# PowerDistributionBoard.net
KiCad netlist of a schematic drawn in EAGLE
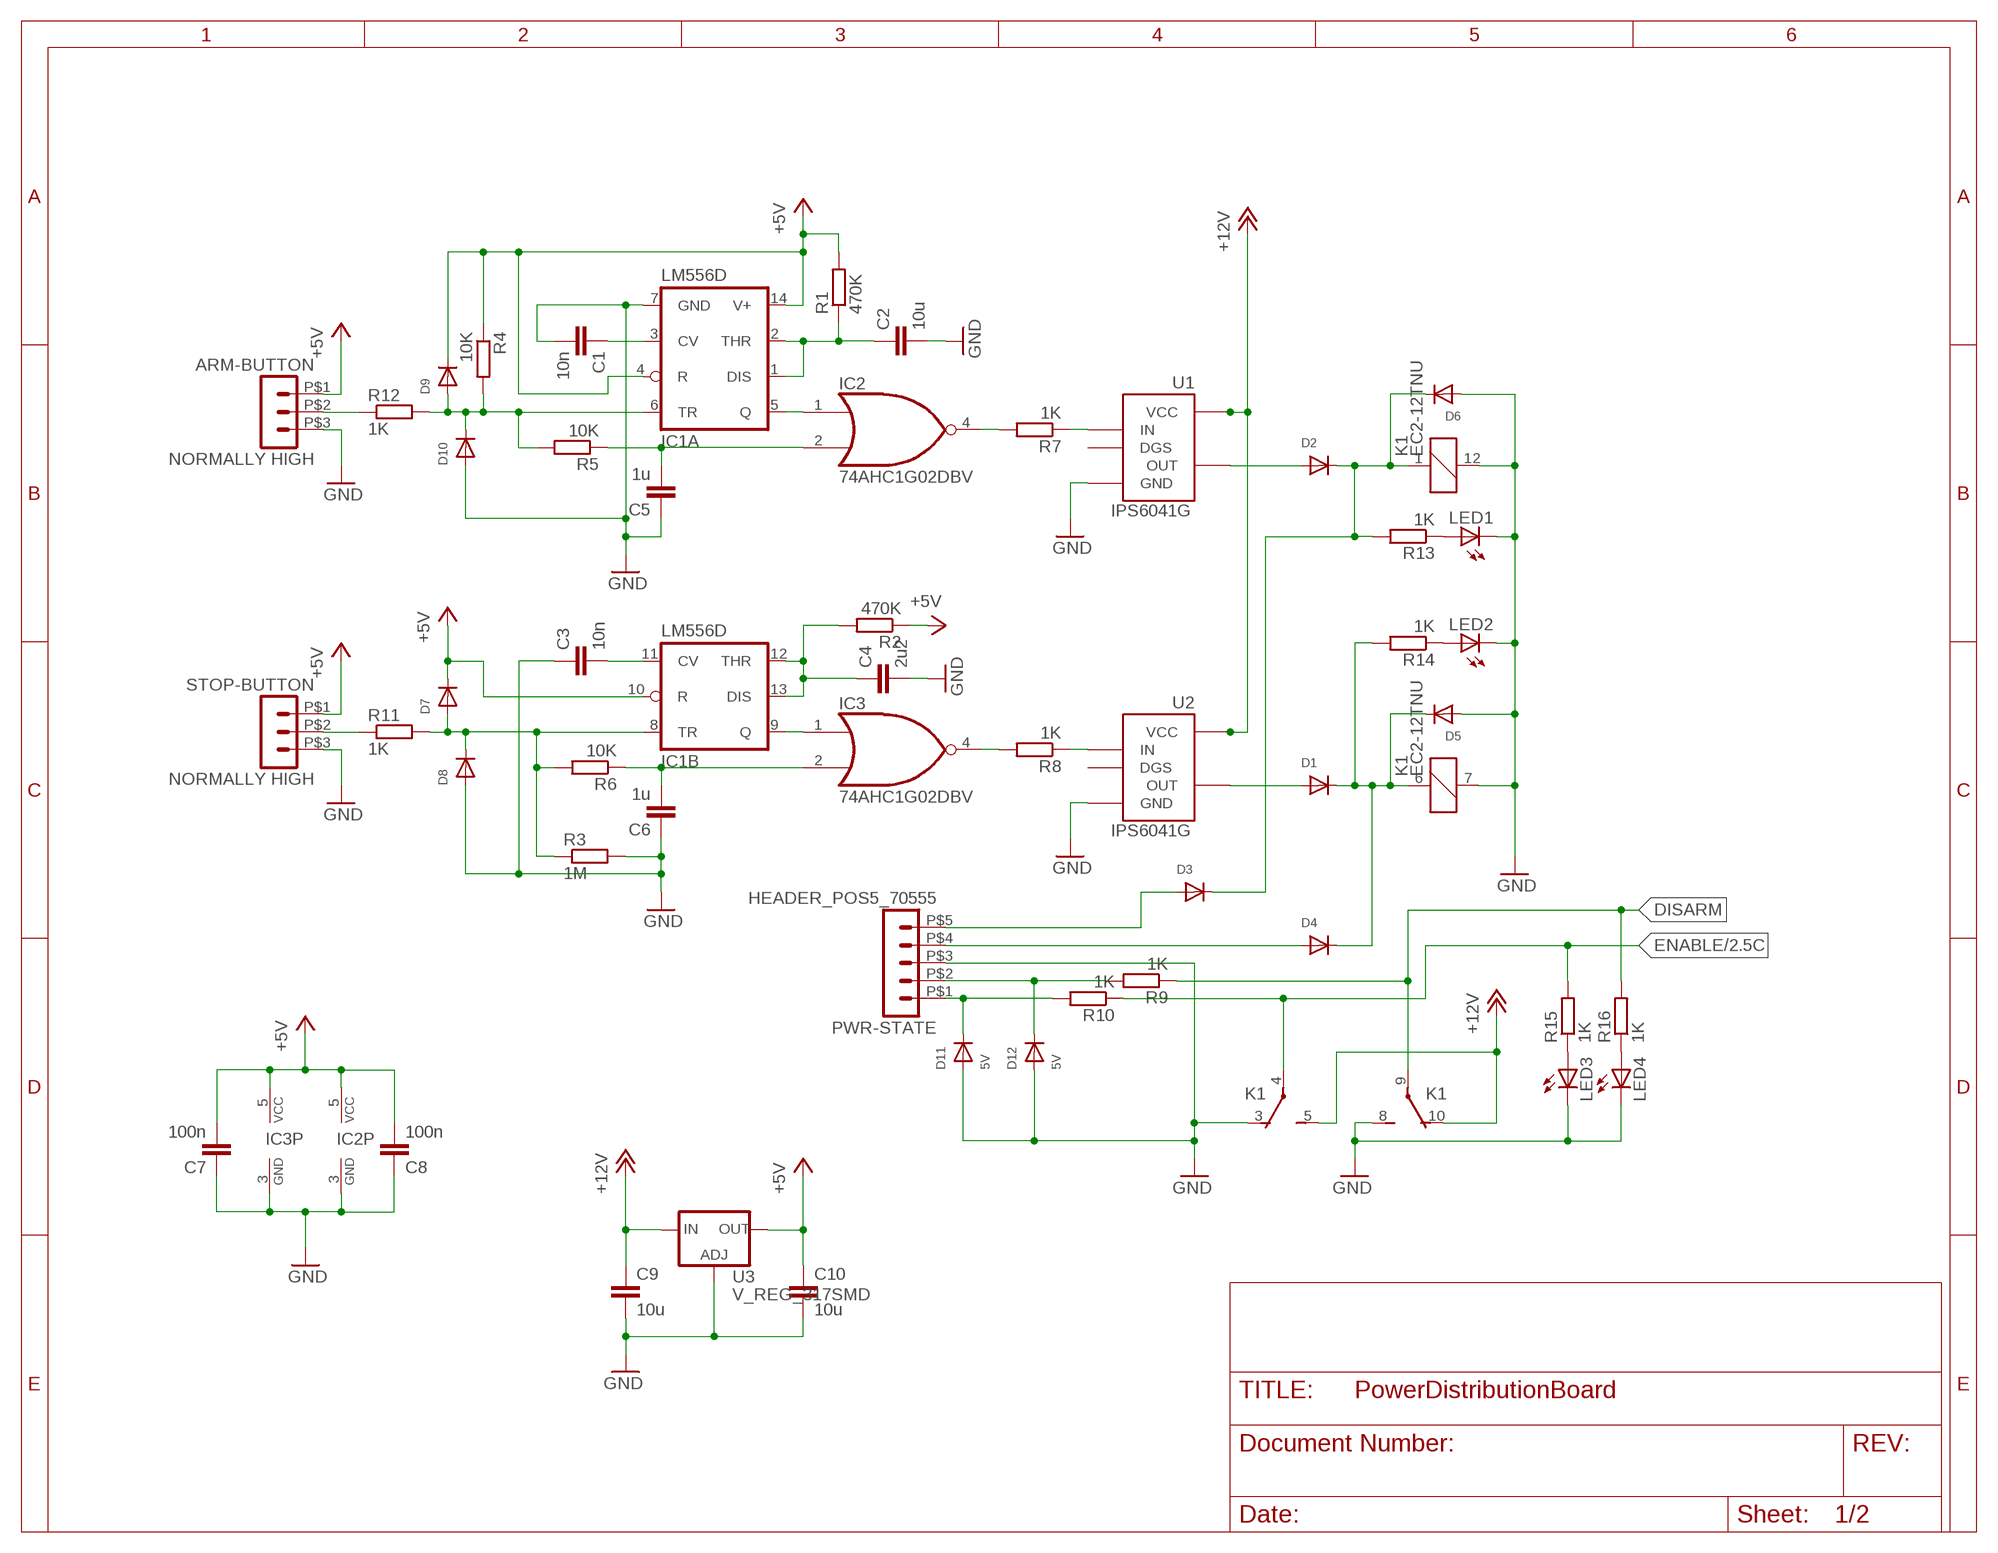
[diagram p0: schematic, sheet 1]
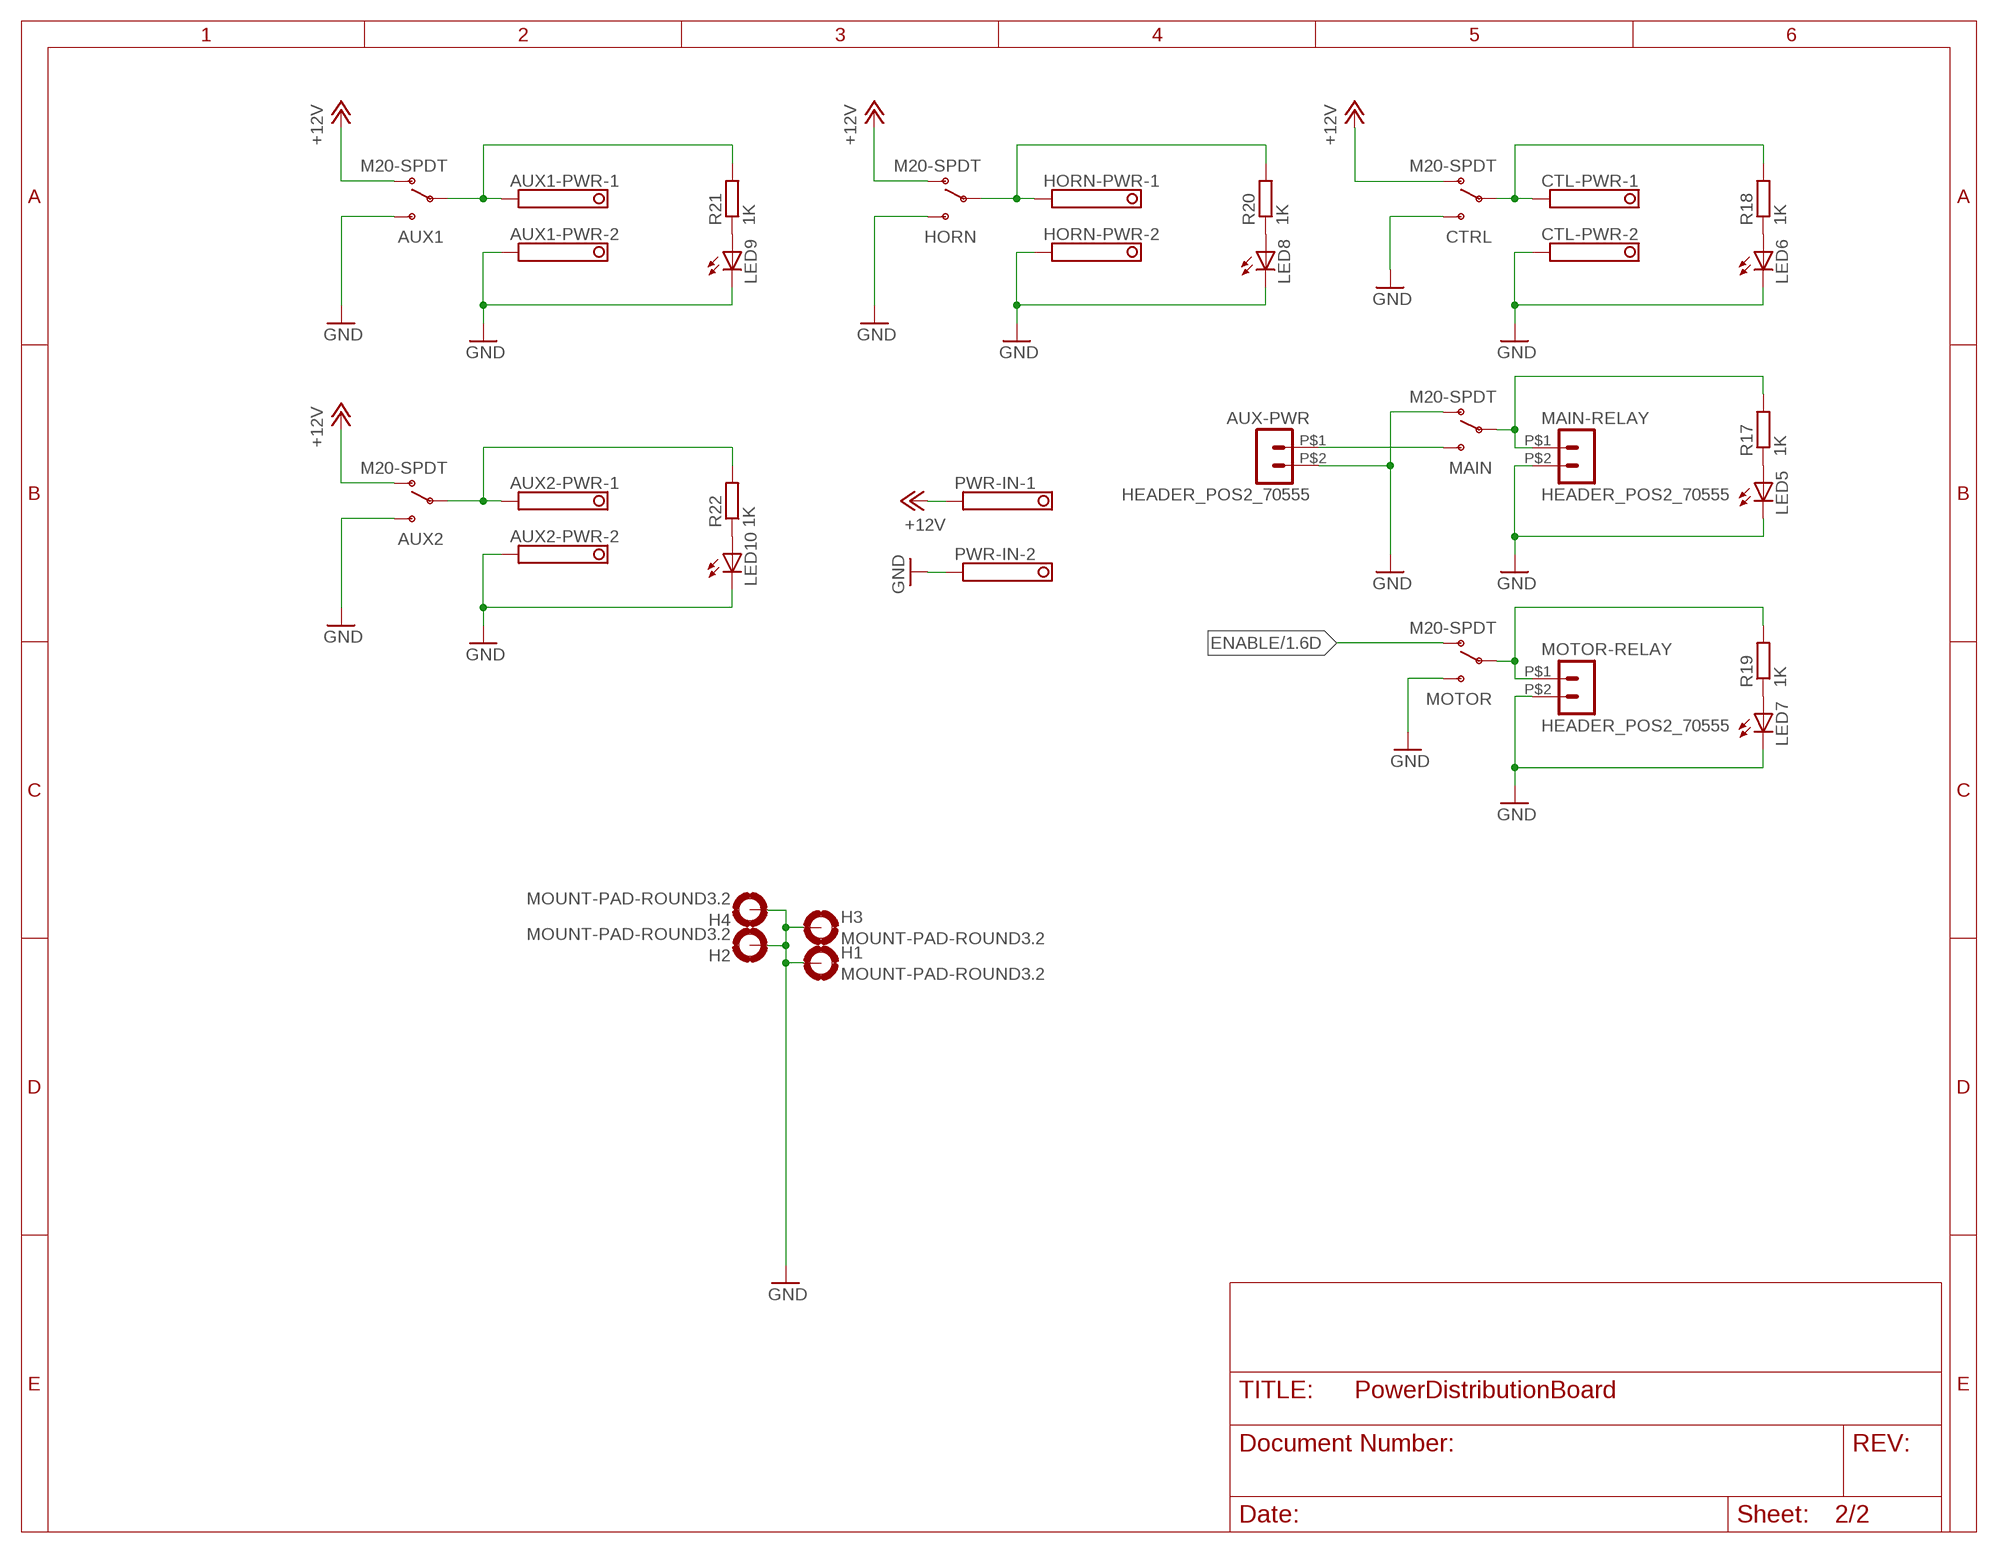
[diagram p1: schematic, sheet 2]

(export (version "E")
  (design (tool "Eeschema 10.0.6"))
  (components
    (comp (ref "ARM-BUTTON")
      (value "NORMALLY HIGH")
      (footprint "eagle-import:70555-POS3")
      (fields (field (name "PARTNO") "0705550037"))
      (libsource (lib "eagle-import") (part "HEADER_POS3_?70555"))
    )
    (comp (ref "C1")
      (value "10n")
      (footprint "eagle-import:C0603")
      (fields (field (name "PARTNO") "CL10B103KB8NCNC"))
      (libsource (lib "eagle-import") (part "C-EUC0603"))
    )
    (comp (ref "C2")
      (value "10u")
      (footprint "eagle-import:C0603")
      (fields (field (name "PARTNO") "C1608JB1E106M080AC"))
      (libsource (lib "eagle-import") (part "C-EUC0603"))
    )
    (comp (ref "C3")
      (value "10n")
      (footprint "eagle-import:C0603")
      (fields (field (name "PARTNO") "CL10B103KB8NCNC"))
      (libsource (lib "eagle-import") (part "C-EUC0603"))
    )
    (comp (ref "C4")
      (value "2u2")
      (footprint "eagle-import:C0603")
      (fields (field (name "PARTNO") "TMK107ABJ225KA-T"))
      (libsource (lib "eagle-import") (part "C-EUC0603"))
    )
    (comp (ref "C5")
      (value "1u")
      (footprint "eagle-import:C0603")
      (fields (field (name "PARTNO") "UMK107BJ105KA-T"))
      (libsource (lib "eagle-import") (part "C-EUC0603"))
    )
    (comp (ref "C6")
      (value "1u")
      (footprint "eagle-import:C0603")
      (fields (field (name "PARTNO") "UMK107BJ105KA-T"))
      (libsource (lib "eagle-import") (part "C-EUC0603"))
    )
    (comp (ref "C7")
      (value "100n")
      (footprint "eagle-import:C0603")
      (fields (field (name "PARTNO") "CC0603ZRY5V9BB104"))
      (libsource (lib "eagle-import") (part "C-EUC0603"))
    )
    (comp (ref "C8")
      (value "100n")
      (footprint "eagle-import:C0603")
      (fields (field (name "PARTNO") "CC0603ZRY5V9BB104"))
      (libsource (lib "eagle-import") (part "C-EUC0603"))
    )
    (comp (ref "C9")
      (value "10u")
      (footprint "eagle-import:C1206")
      (fields (field (name "PARTNO") "C3216X5R1E106M"))
      (libsource (lib "eagle-import") (part "C-EUC1206"))
    )
    (comp (ref "C10")
      (value "10u")
      (footprint "eagle-import:C1206")
      (fields (field (name "PARTNO") "C3216X5R1E106M"))
      (libsource (lib "eagle-import") (part "C-EUC1206"))
    )
    (comp (ref "D1")
      (value "DIODESOD-123")
      (footprint "eagle-import:SOD-123")
      (fields (field (name "PARTNO") "CDBW140-G"))
      (libsource (lib "eagle-import") (part "DIODESOD-123"))
    )
    (comp (ref "D2")
      (value "DIODESOD-123")
      (footprint "eagle-import:SOD-123")
      (fields (field (name "PARTNO") "CDBW140-G"))
      (libsource (lib "eagle-import") (part "DIODESOD-123"))
    )
    (comp (ref "D3")
      (value "DIODESOD-123")
      (footprint "eagle-import:SOD-123")
      (fields (field (name "PARTNO") "CDBW140-G"))
      (libsource (lib "eagle-import") (part "DIODESOD-123"))
    )
    (comp (ref "D4")
      (value "DIODESOD-123")
      (footprint "eagle-import:SOD-123")
      (fields (field (name "PARTNO") "CDBW140-G"))
      (libsource (lib "eagle-import") (part "DIODESOD-123"))
    )
    (comp (ref "D5")
      (value "DIODESOD-123")
      (footprint "eagle-import:SOD-123")
      (fields (field (name "PARTNO") "CDBW140-G"))
      (libsource (lib "eagle-import") (part "DIODESOD-123"))
    )
    (comp (ref "D6")
      (value "DIODESOD-123")
      (footprint "eagle-import:SOD-123")
      (fields (field (name "PARTNO") "CDBW140-G"))
      (libsource (lib "eagle-import") (part "DIODESOD-123"))
    )
    (comp (ref "D7")
      (value "DIODESOD-123")
      (footprint "eagle-import:SOD-123")
      (fields (field (name "PARTNO") "CDBW140-G"))
      (libsource (lib "eagle-import") (part "DIODESOD-123"))
    )
    (comp (ref "D8")
      (value "DIODESOD-123")
      (footprint "eagle-import:SOD-123")
      (fields (field (name "PARTNO") "CDBW140-G"))
      (libsource (lib "eagle-import") (part "DIODESOD-123"))
    )
    (comp (ref "D9")
      (value "DIODESOD-123")
      (footprint "eagle-import:SOD-123")
      (fields (field (name "PARTNO") "CDBW140-G"))
      (libsource (lib "eagle-import") (part "DIODESOD-123"))
    )
    (comp (ref "D10")
      (value "DIODESOD-123")
      (footprint "eagle-import:SOD-123")
      (fields (field (name "PARTNO") "CDBW140-G"))
      (libsource (lib "eagle-import") (part "DIODESOD-123"))
    )
    (comp (ref "D11")
      (value "5V")
      (footprint "eagle-import:SOD-123")
      (fields (field (name "PARTNO") "SMF5.0A"))
      (libsource (lib "eagle-import") (part "DIODESOD-123"))
    )
    (comp (ref "D12")
      (value "5V")
      (footprint "eagle-import:SOD-123")
      (fields (field (name "PARTNO") "SMF5.0A"))
      (libsource (lib "eagle-import") (part "DIODESOD-123"))
    )
    (comp (ref "IC1")
      (value "LM556D")
      (footprint "eagle-import:SO14")
      (fields (field (name "PARTNO") "LM556CM"))
      (libsource (lib "eagle-import") (part "556DLM"))
    )
    (comp (ref "IC2")
      (value "74AHC1G02DBV")
      (footprint "eagle-import:SOT23-5")
      (fields (field (name "PARTNO") "SN74AHC1G02DBVR"))
      (libsource (lib "eagle-import") (part "741G02DBVAHC"))
    )
    (comp (ref "IC3")
      (value "74AHC1G02DBV")
      (footprint "eagle-import:SOT23-5")
      (fields (field (name "PARTNO") "SN74AHC1G02DBVR"))
      (libsource (lib "eagle-import") (part "741G02DBVAHC"))
    )
    (comp (ref "K1")
      (value "EC2-12TNU")
      (footprint "eagle-import:EC2-_TNU")
      (fields (field (name "PARTNO") "EC2-12TNU"))
      (libsource (lib "eagle-import") (part "EC2-12TNU"))
    )
    (comp (ref "LED1")
      (value "LEDCHIP-LED0805")
      (footprint "eagle-import:CHIP-LED0805")
      (fields (field (name "PARTNO") "LG R971-KN-1"))
      (libsource (lib "eagle-import") (part "LEDCHIP-LED0805"))
    )
    (comp (ref "LED2")
      (value "LEDCHIP-LED0805")
      (footprint "eagle-import:CHIP-LED0805")
      (fields (field (name "PARTNO") "LG R971-KN-1"))
      (libsource (lib "eagle-import") (part "LEDCHIP-LED0805"))
    )
    (comp (ref "LED3")
      (value "LEDCHIP-LED0805")
      (footprint "eagle-import:CHIP-LED0805")
      (fields (field (name "PARTNO") "LG R971-KN-1"))
      (libsource (lib "eagle-import") (part "LEDCHIP-LED0805"))
    )
    (comp (ref "LED4")
      (value "LEDCHIP-LED0805")
      (footprint "eagle-import:CHIP-LED0805")
      (fields (field (name "PARTNO") "LG R971-KN-1"))
      (libsource (lib "eagle-import") (part "LEDCHIP-LED0805"))
    )
    (comp (ref "PWR-STATE")
      (value "HEADER_POS5_70555")
      (footprint "eagle-import:70555-POS5")
      (fields (field (name "PARTNO") "0705550039"))
      (libsource (lib "eagle-import") (part "HEADER_POS5_?70555"))
    )
    (comp (ref "R1")
      (value "470K")
      (footprint "eagle-import:R0603")
      (fields (field (name "PARTNO") "MCR03FZPEJ474"))
      (libsource (lib "eagle-import") (part "R-EU_R0603"))
    )
    (comp (ref "R2")
      (value "470K")
      (footprint "eagle-import:R0603")
      (fields (field (name "PARTNO") "MCR03FZPEJ474"))
      (libsource (lib "eagle-import") (part "R-EU_R0603"))
    )
    (comp (ref "R3")
      (value "1M")
      (footprint "eagle-import:R0603")
      (fields (field (name "PARTNO") "MCT06030C1004FP500"))
      (libsource (lib "eagle-import") (part "R-EU_R0603"))
    )
    (comp (ref "R4")
      (value "10K")
      (footprint "eagle-import:R0603")
      (fields (field (name "PARTNO") "RMCF0603FT10K0"))
      (libsource (lib "eagle-import") (part "R-EU_R0603"))
    )
    (comp (ref "R5")
      (value "10K")
      (footprint "eagle-import:R0603")
      (fields (field (name "PARTNO") "RMCF0603FT10K0"))
      (libsource (lib "eagle-import") (part "R-EU_R0603"))
    )
    (comp (ref "R6")
      (value "10K")
      (footprint "eagle-import:R0603")
      (fields (field (name "PARTNO") "RMCF0603FT10K0"))
      (libsource (lib "eagle-import") (part "R-EU_R0603"))
    )
    (comp (ref "R7")
      (value "1K")
      (footprint "eagle-import:R0603")
      (fields (field (name "PARTNO") "RMCF0603FT1K00"))
      (libsource (lib "eagle-import") (part "R-EU_R0603"))
    )
    (comp (ref "R8")
      (value "1K")
      (footprint "eagle-import:R0603")
      (fields (field (name "PARTNO") "RMCF0603FT1K00"))
      (libsource (lib "eagle-import") (part "R-EU_R0603"))
    )
    (comp (ref "R9")
      (value "1K")
      (footprint "eagle-import:R0603")
      (fields (field (name "PARTNO") "RMCF0603FT1K00"))
      (libsource (lib "eagle-import") (part "R-EU_R0603"))
    )
    (comp (ref "R10")
      (value "1K")
      (footprint "eagle-import:R0603")
      (fields (field (name "PARTNO") "RMCF0603FT1K00"))
      (libsource (lib "eagle-import") (part "R-EU_R0603"))
    )
    (comp (ref "R11")
      (value "1K")
      (footprint "eagle-import:R0603")
      (fields (field (name "PARTNO") "RMCF0603FT1K00"))
      (libsource (lib "eagle-import") (part "R-EU_R0603"))
    )
    (comp (ref "R12")
      (value "1K")
      (footprint "eagle-import:R0603")
      (fields (field (name "PARTNO") "RMCF0603FT1K00"))
      (libsource (lib "eagle-import") (part "R-EU_R0603"))
    )
    (comp (ref "R13")
      (value "1K")
      (footprint "eagle-import:R0603")
      (fields (field (name "PARTNO") "RMCF0603FT1K00"))
      (libsource (lib "eagle-import") (part "R-EU_R0603"))
    )
    (comp (ref "R14")
      (value "1K")
      (footprint "eagle-import:R0603")
      (fields (field (name "PARTNO") "RMCF0603FT1K00"))
      (libsource (lib "eagle-import") (part "R-EU_R0603"))
    )
    (comp (ref "R15")
      (value "1K")
      (footprint "eagle-import:R0603")
      (fields (field (name "PARTNO") "RMCF0603FT1K00"))
      (libsource (lib "eagle-import") (part "R-EU_R0603"))
    )
    (comp (ref "R16")
      (value "1K")
      (footprint "eagle-import:R0603")
      (fields (field (name "PARTNO") "RMCF0603FT1K00"))
      (libsource (lib "eagle-import") (part "R-EU_R0603"))
    )
    (comp (ref "STOP-BUTTON")
      (value "NORMALLY HIGH")
      (footprint "eagle-import:70555-POS3")
      (fields (field (name "PARTNO") "0705550037"))
      (libsource (lib "eagle-import") (part "HEADER_POS3_?70555"))
    )
    (comp (ref "U1")
      (value "IPS6041G")
      (footprint "eagle-import:SO08")
      (fields (field (name "PARTNO") "IPS6041GPBF"))
      (libsource (lib "eagle-import") (part "IPS6041G"))
    )
    (comp (ref "U2")
      (value "IPS6041G")
      (footprint "eagle-import:SO08")
      (fields (field (name "PARTNO") "IPS6041GPBF"))
      (libsource (lib "eagle-import") (part "IPS6041G"))
    )
    (comp (ref "U3")
      (value "V_REG_317SMD")
      (footprint "eagle-import:SOT223")
      (fields (field (name "PARTNO") "NCP1117ST50T3G"))
      (libsource (lib "eagle-import") (part "V_REG_317SMD"))
    )
    (comp (ref "AUX-PWR")
      (value "HEADER_POS2_70555")
      (footprint "eagle-import:70555-POS2")
      (fields (field (name "PARTNO") "0705550036"))
      (libsource (lib "eagle-import") (part "HEADER_POS2_?70555"))
    )
    (comp (ref "AUX1")
      (value "M20-SPDT")
      (footprint "eagle-import:M20-SPDT")
      (fields (field (name "PARTNO") "M2012LL1W01"))
      (libsource (lib "eagle-import") (part "M20-SPDT"))
    )
    (comp (ref "AUX1-PWR")
      (value "1751248")
      (footprint "eagle-import:1751248")
      (fields (field (name "PARTNO") "1751248"))
      (libsource (lib "eagle-import") (part "1751248"))
    )
    (comp (ref "AUX2")
      (value "M20-SPDT")
      (footprint "eagle-import:M20-SPDT")
      (fields (field (name "PARTNO") "M2012LL1W01"))
      (libsource (lib "eagle-import") (part "M20-SPDT"))
    )
    (comp (ref "AUX2-PWR")
      (value "1751248")
      (footprint "eagle-import:1751248")
      (fields (field (name "PARTNO") "1751248"))
      (libsource (lib "eagle-import") (part "1751248"))
    )
    (comp (ref "CTL-PWR")
      (value "1751248")
      (footprint "eagle-import:1751248")
      (fields (field (name "PARTNO") "1751248"))
      (libsource (lib "eagle-import") (part "1751248"))
    )
    (comp (ref "CTRL")
      (value "M20-SPDT")
      (footprint "eagle-import:M20-SPDT")
      (fields (field (name "PARTNO") "M2012LL1W01"))
      (libsource (lib "eagle-import") (part "M20-SPDT"))
    )
    (comp (ref "H1")
      (value "MOUNT-PAD-ROUND3.2")
      (footprint "eagle-import:3,2-PAD")
      (libsource (lib "eagle-import") (part "MOUNT-PAD-ROUND3.2"))
    )
    (comp (ref "H2")
      (value "MOUNT-PAD-ROUND3.2")
      (footprint "eagle-import:3,2-PAD")
      (libsource (lib "eagle-import") (part "MOUNT-PAD-ROUND3.2"))
    )
    (comp (ref "H3")
      (value "MOUNT-PAD-ROUND3.2")
      (footprint "eagle-import:3,2-PAD")
      (libsource (lib "eagle-import") (part "MOUNT-PAD-ROUND3.2"))
    )
    (comp (ref "H4")
      (value "MOUNT-PAD-ROUND3.2")
      (footprint "eagle-import:3,2-PAD")
      (libsource (lib "eagle-import") (part "MOUNT-PAD-ROUND3.2"))
    )
    (comp (ref "HORN")
      (value "M20-SPDT")
      (footprint "eagle-import:M20-SPDT")
      (fields (field (name "PARTNO") "M2012LL1W01"))
      (libsource (lib "eagle-import") (part "M20-SPDT"))
    )
    (comp (ref "HORN-PWR")
      (value "1751248")
      (footprint "eagle-import:1751248")
      (fields (field (name "PARTNO") "1751248"))
      (libsource (lib "eagle-import") (part "1751248"))
    )
    (comp (ref "LED5")
      (value "LEDCHIP-LED0805")
      (footprint "eagle-import:CHIP-LED0805")
      (fields (field (name "PARTNO") "LG R971-KN-1"))
      (libsource (lib "eagle-import") (part "LEDCHIP-LED0805"))
    )
    (comp (ref "LED6")
      (value "LEDCHIP-LED0805")
      (footprint "eagle-import:CHIP-LED0805")
      (fields (field (name "PARTNO") "LG R971-KN-1"))
      (libsource (lib "eagle-import") (part "LEDCHIP-LED0805"))
    )
    (comp (ref "LED7")
      (value "LEDCHIP-LED0805")
      (footprint "eagle-import:CHIP-LED0805")
      (fields (field (name "PARTNO") "LG R971-KN-1"))
      (libsource (lib "eagle-import") (part "LEDCHIP-LED0805"))
    )
    (comp (ref "LED8")
      (value "LEDCHIP-LED0805")
      (footprint "eagle-import:CHIP-LED0805")
      (fields (field (name "PARTNO") "LG R971-KN-1"))
      (libsource (lib "eagle-import") (part "LEDCHIP-LED0805"))
    )
    (comp (ref "LED9")
      (value "LEDCHIP-LED0805")
      (footprint "eagle-import:CHIP-LED0805")
      (fields (field (name "PARTNO") "LG R971-KN-1"))
      (libsource (lib "eagle-import") (part "LEDCHIP-LED0805"))
    )
    (comp (ref "LED10")
      (value "LEDCHIP-LED0805")
      (footprint "eagle-import:CHIP-LED0805")
      (fields (field (name "PARTNO") "LG R971-KN-1"))
      (libsource (lib "eagle-import") (part "LEDCHIP-LED0805"))
    )
    (comp (ref "MAIN")
      (value "M20-SPDT")
      (footprint "eagle-import:M20-SPDT")
      (fields (field (name "PARTNO") "M2012LL1W01"))
      (libsource (lib "eagle-import") (part "M20-SPDT"))
    )
    (comp (ref "MAIN-RELAY")
      (value "HEADER_POS2_70555")
      (footprint "eagle-import:70555-POS2")
      (fields (field (name "PARTNO") "0705550036"))
      (libsource (lib "eagle-import") (part "HEADER_POS2_?70555"))
    )
    (comp (ref "MOTOR")
      (value "M20-SPDT")
      (footprint "eagle-import:M20-SPDT")
      (fields (field (name "PARTNO") "M2012LL1W01"))
      (libsource (lib "eagle-import") (part "M20-SPDT"))
    )
    (comp (ref "MOTOR-RELAY")
      (value "HEADER_POS2_70555")
      (footprint "eagle-import:70555-POS2")
      (fields (field (name "PARTNO") "0705550036"))
      (libsource (lib "eagle-import") (part "HEADER_POS2_?70555"))
    )
    (comp (ref "PWR-IN")
      (value "1751248")
      (footprint "eagle-import:1751248")
      (fields (field (name "PARTNO") "1751248"))
      (libsource (lib "eagle-import") (part "1751248"))
    )
    (comp (ref "R17")
      (value "1K")
      (footprint "eagle-import:R0603")
      (fields (field (name "PARTNO") "RMCF0603FT1K00"))
      (libsource (lib "eagle-import") (part "R-EU_R0603"))
    )
    (comp (ref "R18")
      (value "1K")
      (footprint "eagle-import:R0603")
      (fields (field (name "PARTNO") "RMCF0603FT1K00"))
      (libsource (lib "eagle-import") (part "R-EU_R0603"))
    )
    (comp (ref "R19")
      (value "1K")
      (footprint "eagle-import:R0603")
      (fields (field (name "PARTNO") "RMCF0603FT1K00"))
      (libsource (lib "eagle-import") (part "R-EU_R0603"))
    )
    (comp (ref "R20")
      (value "1K")
      (footprint "eagle-import:R0603")
      (fields (field (name "PARTNO") "RMCF0603FT1K00"))
      (libsource (lib "eagle-import") (part "R-EU_R0603"))
    )
    (comp (ref "R21")
      (value "1K")
      (footprint "eagle-import:R0603")
      (fields (field (name "PARTNO") "RMCF0603FT1K00"))
      (libsource (lib "eagle-import") (part "R-EU_R0603"))
    )
    (comp (ref "R22")
      (value "1K")
      (footprint "eagle-import:R0603")
      (fields (field (name "PARTNO") "RMCF0603FT1K00"))
      (libsource (lib "eagle-import") (part "R-EU_R0603"))
    )
  )
  (nets
    (net (code "1") (name "+5V") (class "Default")
      (node (ref "ARM-BUTTON") (pin "P$1") (pinfunction "1_P$1") (pintype "passive"))
      (node (ref "C10") (pin "1") (pinfunction "1_1") (pintype "passive"))
      (node (ref "C7") (pin "2") (pinfunction "2_2") (pintype "passive"))
      (node (ref "C8") (pin "2") (pinfunction "2_2") (pintype "passive"))
      (node (ref "D7") (pin "C") (pinfunction "C_C") (pintype "passive"))
      (node (ref "D9") (pin "C") (pinfunction "C_C") (pintype "passive"))
      (node (ref "IC1") (pin "10") (pinfunction "R_10") (pintype "input"))
      (node (ref "IC1") (pin "14") (pinfunction "V+_14") (pintype "power_in"))
      (node (ref "IC1") (pin "4") (pinfunction "R_4") (pintype "input"))
      (node (ref "IC2") (pin "5") (pinfunction "VCC_5") (pintype "power_in"))
      (node (ref "IC3") (pin "5") (pinfunction "VCC_5") (pintype "power_in"))
      (node (ref "R1") (pin "2") (pinfunction "2_2") (pintype "passive"))
      (node (ref "R2") (pin "1") (pinfunction "1_1") (pintype "passive"))
      (node (ref "R4") (pin "1") (pinfunction "1_1") (pintype "passive"))
      (node (ref "STOP-BUTTON") (pin "P$1") (pinfunction "1_P$1") (pintype "passive"))
      (node (ref "U3") (pin "2") (pinfunction "OUT_2") (pintype "output"))
    )
    (net (code "2") (name "+12V") (class "Default")
      (node (ref "AUX1") (pin "1") (pinfunction "O_1") (pintype "passive"))
      (node (ref "AUX2") (pin "1") (pinfunction "O_1") (pintype "passive"))
      (node (ref "C9") (pin "1") (pinfunction "1_1") (pintype "passive"))
      (node (ref "CTRL") (pin "1") (pinfunction "O_1") (pintype "passive"))
      (node (ref "HORN") (pin "1") (pinfunction "O_1") (pintype "passive"))
      (node (ref "K1") (pin "10") (pinfunction "O_10") (pintype "passive"))
      (node (ref "K1") (pin "5") (pinfunction "S_5") (pintype "passive"))
      (node (ref "PWR-IN") (pin "1") (pinfunction "K_1") (pintype "passive"))
      (node (ref "U1") (pin "5") (pinfunction "VCC_5") (pintype "passive"))
      (node (ref "U1") (pin "6") (pinfunction "VCC_6") (pintype "passive"))
      (node (ref "U1") (pin "7") (pinfunction "VCC_7") (pintype "passive"))
      (node (ref "U1") (pin "8") (pinfunction "VCC_8") (pintype "passive"))
      (node (ref "U2") (pin "5") (pinfunction "VCC_5") (pintype "passive"))
      (node (ref "U2") (pin "6") (pinfunction "VCC_6") (pintype "passive"))
      (node (ref "U2") (pin "7") (pinfunction "VCC_7") (pintype "passive"))
      (node (ref "U2") (pin "8") (pinfunction "VCC_8") (pintype "passive"))
      (node (ref "U3") (pin "3") (pinfunction "IN_3") (pintype "input"))
    )
    (net (code "3") (name "DISARM") (class "Default")
      (node (ref "K1") (pin "9") (pinfunction "P_9") (pintype "passive"))
      (node (ref "R16") (pin "2") (pinfunction "2_2") (pintype "passive"))
      (node (ref "R9") (pin "1") (pinfunction "1_1") (pintype "passive"))
    )
    (net (code "4") (name "ENABLE") (class "Default")
      (node (ref "K1") (pin "4") (pinfunction "P_4") (pintype "passive"))
      (node (ref "MOTOR") (pin "1") (pinfunction "O_1") (pintype "passive"))
      (node (ref "R10") (pin "1") (pinfunction "1_1") (pintype "passive"))
      (node (ref "R15") (pin "2") (pinfunction "2_2") (pintype "passive"))
    )
    (net (code "5") (name "GND") (class "Default")
      (node (ref "ARM-BUTTON") (pin "P$3") (pinfunction "3_P$3") (pintype "passive"))
      (node (ref "AUX-PWR") (pin "P$2") (pinfunction "2_P$2") (pintype "passive"))
      (node (ref "AUX1") (pin "3") (pinfunction "S_3") (pintype "passive"))
      (node (ref "AUX1-PWR") (pin "2") (pinfunction "K_2") (pintype "passive"))
      (node (ref "AUX2") (pin "3") (pinfunction "S_3") (pintype "passive"))
      (node (ref "AUX2-PWR") (pin "2") (pinfunction "K_2") (pintype "passive"))
      (node (ref "C1") (pin "2") (pinfunction "2_2") (pintype "passive"))
      (node (ref "C10") (pin "2") (pinfunction "2_2") (pintype "passive"))
      (node (ref "C2") (pin "2") (pinfunction "2_2") (pintype "passive"))
      (node (ref "C3") (pin "1") (pinfunction "1_1") (pintype "passive"))
      (node (ref "C4") (pin "2") (pinfunction "2_2") (pintype "passive"))
      (node (ref "C5") (pin "1") (pinfunction "1_1") (pintype "passive"))
      (node (ref "C6") (pin "1") (pinfunction "1_1") (pintype "passive"))
      (node (ref "C7") (pin "1") (pinfunction "1_1") (pintype "passive"))
      (node (ref "C8") (pin "1") (pinfunction "1_1") (pintype "passive"))
      (node (ref "C9") (pin "2") (pinfunction "2_2") (pintype "passive"))
      (node (ref "CTL-PWR") (pin "2") (pinfunction "K_2") (pintype "passive"))
      (node (ref "CTRL") (pin "3") (pinfunction "S_3") (pintype "passive"))
      (node (ref "D10") (pin "A") (pinfunction "A_A") (pintype "passive"))
      (node (ref "D11") (pin "A") (pinfunction "A_A") (pintype "passive"))
      (node (ref "D12") (pin "A") (pinfunction "A_A") (pintype "passive"))
      (node (ref "D5") (pin "A") (pinfunction "A_A") (pintype "passive"))
      (node (ref "D6") (pin "A") (pinfunction "A_A") (pintype "passive"))
      (node (ref "D8") (pin "A") (pinfunction "A_A") (pintype "passive"))
      (node (ref "H1") (pin "B3,2") (pinfunction "MOUNT_B3,2") (pintype "passive"))
      (node (ref "H2") (pin "B3,2") (pinfunction "MOUNT_B3,2") (pintype "passive"))
      (node (ref "H3") (pin "B3,2") (pinfunction "MOUNT_B3,2") (pintype "passive"))
      (node (ref "H4") (pin "B3,2") (pinfunction "MOUNT_B3,2") (pintype "passive"))
      (node (ref "HORN") (pin "3") (pinfunction "S_3") (pintype "passive"))
      (node (ref "HORN-PWR") (pin "2") (pinfunction "K_2") (pintype "passive"))
      (node (ref "IC1") (pin "7") (pinfunction "GND_7") (pintype "power_in"))
      (node (ref "IC2") (pin "3") (pinfunction "GND_3") (pintype "power_in"))
      (node (ref "IC3") (pin "3") (pinfunction "GND_3") (pintype "power_in"))
      (node (ref "K1") (pin "12") (pinfunction "2_12") (pintype "passive"))
      (node (ref "K1") (pin "3") (pinfunction "O_3") (pintype "passive"))
      (node (ref "K1") (pin "7") (pinfunction "2_7") (pintype "passive"))
      (node (ref "K1") (pin "8") (pinfunction "S_8") (pintype "passive"))
      (node (ref "LED1") (pin "C") (pinfunction "C_C") (pintype "passive"))
      (node (ref "LED10") (pin "C") (pinfunction "C_C") (pintype "passive"))
      (node (ref "LED2") (pin "C") (pinfunction "C_C") (pintype "passive"))
      (node (ref "LED3") (pin "C") (pinfunction "C_C") (pintype "passive"))
      (node (ref "LED4") (pin "C") (pinfunction "C_C") (pintype "passive"))
      (node (ref "LED5") (pin "C") (pinfunction "C_C") (pintype "passive"))
      (node (ref "LED6") (pin "C") (pinfunction "C_C") (pintype "passive"))
      (node (ref "LED7") (pin "C") (pinfunction "C_C") (pintype "passive"))
      (node (ref "LED8") (pin "C") (pinfunction "C_C") (pintype "passive"))
      (node (ref "LED9") (pin "C") (pinfunction "C_C") (pintype "passive"))
      (node (ref "MAIN") (pin "1") (pinfunction "O_1") (pintype "passive"))
      (node (ref "MAIN-RELAY") (pin "P$2") (pinfunction "2_P$2") (pintype "passive"))
      (node (ref "MOTOR") (pin "3") (pinfunction "S_3") (pintype "passive"))
      (node (ref "MOTOR-RELAY") (pin "P$2") (pinfunction "2_P$2") (pintype "passive"))
      (node (ref "PWR-IN") (pin "2") (pinfunction "K_2") (pintype "passive"))
      (node (ref "PWR-STATE") (pin "P$3") (pinfunction "3_P$3") (pintype "passive"))
      (node (ref "R3") (pin "2") (pinfunction "2_2") (pintype "passive"))
      (node (ref "STOP-BUTTON") (pin "P$3") (pinfunction "3_P$3") (pintype "passive"))
      (node (ref "U1") (pin "1") (pinfunction "GND_1") (pintype "passive"))
      (node (ref "U2") (pin "1") (pinfunction "GND_1") (pintype "passive"))
      (node (ref "U3") (pin "1") (pinfunction "ADJ_1") (pintype "input"))
    )
    (net (code "6") (name "Net-(ARM-BUTTON-2)") (class "Default")
      (node (ref "ARM-BUTTON") (pin "P$2") (pinfunction "2_P$2") (pintype "passive"))
      (node (ref "R12") (pin "1") (pinfunction "1_1") (pintype "passive"))
    )
    (net (code "7") (name "Net-(AUX-PWR-1)") (class "Default")
      (node (ref "AUX-PWR") (pin "P$1") (pinfunction "1_P$1") (pintype "passive"))
      (node (ref "MAIN") (pin "3") (pinfunction "S_3") (pintype "passive"))
    )
    (net (code "8") (name "Net-(AUX1-P)") (class "Default")
      (node (ref "AUX1") (pin "2") (pinfunction "P_2") (pintype "passive"))
      (node (ref "AUX1-PWR") (pin "1") (pinfunction "K_1") (pintype "passive"))
      (node (ref "R21") (pin "2") (pinfunction "2_2") (pintype "passive"))
    )
    (net (code "9") (name "Net-(AUX2-P)") (class "Default")
      (node (ref "AUX2") (pin "2") (pinfunction "P_2") (pintype "passive"))
      (node (ref "AUX2-PWR") (pin "1") (pinfunction "K_1") (pintype "passive"))
      (node (ref "R22") (pin "2") (pinfunction "2_2") (pintype "passive"))
    )
    (net (code "10") (name "Net-(CTL-PWRA-K)") (class "Default")
      (node (ref "CTL-PWR") (pin "1") (pinfunction "K_1") (pintype "passive"))
      (node (ref "CTRL") (pin "2") (pinfunction "P_2") (pintype "passive"))
      (node (ref "R18") (pin "2") (pinfunction "2_2") (pintype "passive"))
    )
    (net (code "11") (name "Net-(D2-PadC)") (class "Default")
      (node (ref "D2") (pin "C") (pinfunction "C_C") (pintype "passive"))
      (node (ref "D3") (pin "C") (pinfunction "C_C") (pintype "passive"))
      (node (ref "D6") (pin "C") (pinfunction "C_C") (pintype "passive"))
      (node (ref "K1") (pin "1") (pinfunction "1_1") (pintype "passive"))
      (node (ref "R13") (pin "2") (pinfunction "2_2") (pintype "passive"))
    )
    (net (code "12") (name "Net-(HORN-P)") (class "Default")
      (node (ref "HORN") (pin "2") (pinfunction "P_2") (pintype "passive"))
      (node (ref "HORN-PWR") (pin "1") (pinfunction "K_1") (pintype "passive"))
      (node (ref "R20") (pin "2") (pinfunction "2_2") (pintype "passive"))
    )
    (net (code "13") (name "Net-(IC1A-CV)") (class "Default")
      (node (ref "C1") (pin "1") (pinfunction "1_1") (pintype "passive"))
      (node (ref "IC1") (pin "3") (pinfunction "CV_3") (pintype "input"))
    )
    (net (code "14") (name "Net-(IC1A-DIS)") (class "Default")
      (node (ref "C2") (pin "1") (pinfunction "1_1") (pintype "passive"))
      (node (ref "IC1") (pin "1") (pinfunction "DIS_1") (pintype "input"))
      (node (ref "IC1") (pin "2") (pinfunction "THR_2") (pintype "input"))
      (node (ref "R1") (pin "1") (pinfunction "1_1") (pintype "passive"))
    )
    (net (code "15") (name "Net-(IC1A-Q)") (class "Default")
      (node (ref "IC1") (pin "5") (pinfunction "Q_5") (pintype "output"))
      (node (ref "IC2") (pin "1") (pinfunction "I0_1") (pintype "input"))
    )
    (net (code "16") (name "Net-(IC1A-TR)") (class "Default")
      (node (ref "D10") (pin "C") (pinfunction "C_C") (pintype "passive"))
      (node (ref "D9") (pin "A") (pinfunction "A_A") (pintype "passive"))
      (node (ref "IC1") (pin "6") (pinfunction "TR_6") (pintype "input"))
      (node (ref "R12") (pin "2") (pinfunction "2_2") (pintype "passive"))
      (node (ref "R4") (pin "2") (pinfunction "2_2") (pintype "passive"))
      (node (ref "R5") (pin "2") (pinfunction "2_2") (pintype "passive"))
    )
    (net (code "17") (name "Net-(IC1B-CV)") (class "Default")
      (node (ref "C3") (pin "2") (pinfunction "2_2") (pintype "passive"))
      (node (ref "IC1") (pin "11") (pinfunction "CV_11") (pintype "input"))
    )
    (net (code "18") (name "Net-(IC1B-DIS)") (class "Default")
      (node (ref "C4") (pin "1") (pinfunction "1_1") (pintype "passive"))
      (node (ref "IC1") (pin "12") (pinfunction "THR_12") (pintype "input"))
      (node (ref "IC1") (pin "13") (pinfunction "DIS_13") (pintype "input"))
      (node (ref "R2") (pin "2") (pinfunction "2_2") (pintype "passive"))
    )
    (net (code "19") (name "Net-(IC1B-Q)") (class "Default")
      (node (ref "IC1") (pin "9") (pinfunction "Q_9") (pintype "output"))
      (node (ref "IC3") (pin "1") (pinfunction "I0_1") (pintype "input"))
    )
    (net (code "20") (name "Net-(IC1B-TR)") (class "Default")
      (node (ref "D7") (pin "A") (pinfunction "A_A") (pintype "passive"))
      (node (ref "D8") (pin "C") (pinfunction "C_C") (pintype "passive"))
      (node (ref "IC1") (pin "8") (pinfunction "TR_8") (pintype "input"))
      (node (ref "R11") (pin "2") (pinfunction "2_2") (pintype "passive"))
      (node (ref "R3") (pin "1") (pinfunction "1_1") (pintype "passive"))
      (node (ref "R6") (pin "2") (pinfunction "2_2") (pintype "passive"))
    )
    (net (code "21") (name "Net-(IC2A-I1)") (class "Default")
      (node (ref "C5") (pin "2") (pinfunction "2_2") (pintype "passive"))
      (node (ref "IC2") (pin "2") (pinfunction "I1_2") (pintype "input"))
      (node (ref "R5") (pin "1") (pinfunction "1_1") (pintype "passive"))
    )
    (net (code "22") (name "Net-(IC2A-O)") (class "Default")
      (node (ref "IC2") (pin "4") (pinfunction "O_4") (pintype "output"))
      (node (ref "R7") (pin "2") (pinfunction "2_2") (pintype "passive"))
    )
    (net (code "23") (name "Net-(IC3A-I1)") (class "Default")
      (node (ref "C6") (pin "2") (pinfunction "2_2") (pintype "passive"))
      (node (ref "IC3") (pin "2") (pinfunction "I1_2") (pintype "input"))
      (node (ref "R6") (pin "1") (pinfunction "1_1") (pintype "passive"))
    )
    (net (code "24") (name "Net-(IC3A-O)") (class "Default")
      (node (ref "IC3") (pin "4") (pinfunction "O_4") (pintype "output"))
      (node (ref "R8") (pin "2") (pinfunction "2_2") (pintype "passive"))
    )
    (net (code "25") (name "Net-(K1C-1)") (class "Default")
      (node (ref "D1") (pin "C") (pinfunction "C_C") (pintype "passive"))
      (node (ref "D4") (pin "C") (pinfunction "C_C") (pintype "passive"))
      (node (ref "D5") (pin "C") (pinfunction "C_C") (pintype "passive"))
      (node (ref "K1") (pin "6") (pinfunction "1_6") (pintype "passive"))
      (node (ref "R14") (pin "2") (pinfunction "2_2") (pintype "passive"))
    )
    (net (code "26") (name "Net-(LED1-PadA)") (class "Default")
      (node (ref "LED1") (pin "A") (pinfunction "A_A") (pintype "passive"))
      (node (ref "R13") (pin "1") (pinfunction "1_1") (pintype "passive"))
    )
    (net (code "27") (name "Net-(LED2-PadA)") (class "Default")
      (node (ref "LED2") (pin "A") (pinfunction "A_A") (pintype "passive"))
      (node (ref "R14") (pin "1") (pinfunction "1_1") (pintype "passive"))
    )
    (net (code "28") (name "Net-(LED3-PadA)") (class "Default")
      (node (ref "LED3") (pin "A") (pinfunction "A_A") (pintype "passive"))
      (node (ref "R15") (pin "1") (pinfunction "1_1") (pintype "passive"))
    )
    (net (code "29") (name "Net-(LED4-PadA)") (class "Default")
      (node (ref "LED4") (pin "A") (pinfunction "A_A") (pintype "passive"))
      (node (ref "R16") (pin "1") (pinfunction "1_1") (pintype "passive"))
    )
    (net (code "30") (name "Net-(LED5-PadA)") (class "Default")
      (node (ref "LED5") (pin "A") (pinfunction "A_A") (pintype "passive"))
      (node (ref "R17") (pin "1") (pinfunction "1_1") (pintype "passive"))
    )
    (net (code "31") (name "Net-(LED6-PadA)") (class "Default")
      (node (ref "LED6") (pin "A") (pinfunction "A_A") (pintype "passive"))
      (node (ref "R18") (pin "1") (pinfunction "1_1") (pintype "passive"))
    )
    (net (code "32") (name "Net-(LED7-PadA)") (class "Default")
      (node (ref "LED7") (pin "A") (pinfunction "A_A") (pintype "passive"))
      (node (ref "R19") (pin "1") (pinfunction "1_1") (pintype "passive"))
    )
    (net (code "33") (name "Net-(LED8-PadA)") (class "Default")
      (node (ref "LED8") (pin "A") (pinfunction "A_A") (pintype "passive"))
      (node (ref "R20") (pin "1") (pinfunction "1_1") (pintype "passive"))
    )
    (net (code "34") (name "Net-(LED9-PadA)") (class "Default")
      (node (ref "LED9") (pin "A") (pinfunction "A_A") (pintype "passive"))
      (node (ref "R21") (pin "1") (pinfunction "1_1") (pintype "passive"))
    )
    (net (code "35") (name "Net-(LED10-PadA)") (class "Default")
      (node (ref "LED10") (pin "A") (pinfunction "A_A") (pintype "passive"))
      (node (ref "R22") (pin "1") (pinfunction "1_1") (pintype "passive"))
    )
    (net (code "36") (name "Net-(MAIN-P)") (class "Default")
      (node (ref "MAIN") (pin "2") (pinfunction "P_2") (pintype "passive"))
      (node (ref "MAIN-RELAY") (pin "P$1") (pinfunction "1_P$1") (pintype "passive"))
      (node (ref "R17") (pin "2") (pinfunction "2_2") (pintype "passive"))
    )
    (net (code "37") (name "Net-(MOTOR-P)") (class "Default")
      (node (ref "MOTOR") (pin "2") (pinfunction "P_2") (pintype "passive"))
      (node (ref "MOTOR-RELAY") (pin "P$1") (pinfunction "1_P$1") (pintype "passive"))
      (node (ref "R19") (pin "2") (pinfunction "2_2") (pintype "passive"))
    )
    (net (code "38") (name "Net-(PWR-STATE-1)") (class "Default")
      (node (ref "D11") (pin "C") (pinfunction "C_C") (pintype "passive"))
      (node (ref "PWR-STATE") (pin "P$1") (pinfunction "1_P$1") (pintype "passive"))
      (node (ref "R10") (pin "2") (pinfunction "2_2") (pintype "passive"))
    )
    (net (code "39") (name "Net-(PWR-STATE-2)") (class "Default")
      (node (ref "D12") (pin "C") (pinfunction "C_C") (pintype "passive"))
      (node (ref "PWR-STATE") (pin "P$2") (pinfunction "2_P$2") (pintype "passive"))
      (node (ref "R9") (pin "2") (pinfunction "2_2") (pintype "passive"))
    )
    (net (code "40") (name "Net-(PWR-STATE-4)") (class "Default")
      (node (ref "D4") (pin "A") (pinfunction "A_A") (pintype "passive"))
      (node (ref "PWR-STATE") (pin "P$4") (pinfunction "4_P$4") (pintype "passive"))
    )
    (net (code "41") (name "Net-(PWR-STATE-5)") (class "Default")
      (node (ref "D3") (pin "A") (pinfunction "A_A") (pintype "passive"))
      (node (ref "PWR-STATE") (pin "P$5") (pinfunction "5_P$5") (pintype "passive"))
    )
    (net (code "42") (name "Net-(STOP-BUTTON-2)") (class "Default")
      (node (ref "R11") (pin "1") (pinfunction "1_1") (pintype "passive"))
      (node (ref "STOP-BUTTON") (pin "P$2") (pinfunction "2_P$2") (pintype "passive"))
    )
    (net (code "43") (name "Net-(U1-IN)") (class "Default")
      (node (ref "R7") (pin "1") (pinfunction "1_1") (pintype "passive"))
      (node (ref "U1") (pin "2") (pinfunction "IN_2") (pintype "input"))
    )
    (net (code "44") (name "Net-(U1-OUT)") (class "Default")
      (node (ref "D2") (pin "A") (pinfunction "A_A") (pintype "passive"))
      (node (ref "U1") (pin "4") (pinfunction "OUT_4") (pintype "output"))
    )
    (net (code "45") (name "Net-(U2-IN)") (class "Default")
      (node (ref "R8") (pin "1") (pinfunction "1_1") (pintype "passive"))
      (node (ref "U2") (pin "2") (pinfunction "IN_2") (pintype "input"))
    )
    (net (code "46") (name "Net-(U2-OUT)") (class "Default")
      (node (ref "D1") (pin "A") (pinfunction "A_A") (pintype "passive"))
      (node (ref "U2") (pin "4") (pinfunction "OUT_4") (pintype "output"))
    )
    (net (code "47") (name "unconnected-(U1-DGS-Pad3)") (class "Default")
      (node (ref "U1") (pin "3") (pinfunction "DGS_3") (pintype "output"))
    )
    (net (code "48") (name "unconnected-(U2-DGS-Pad3)") (class "Default")
      (node (ref "U2") (pin "3") (pinfunction "DGS_3") (pintype "output"))
    )
  )
)
